# Adafruit_nRF52_Bluefruit_Feather.net
KiCad netlist of a schematic drawn in EAGLE
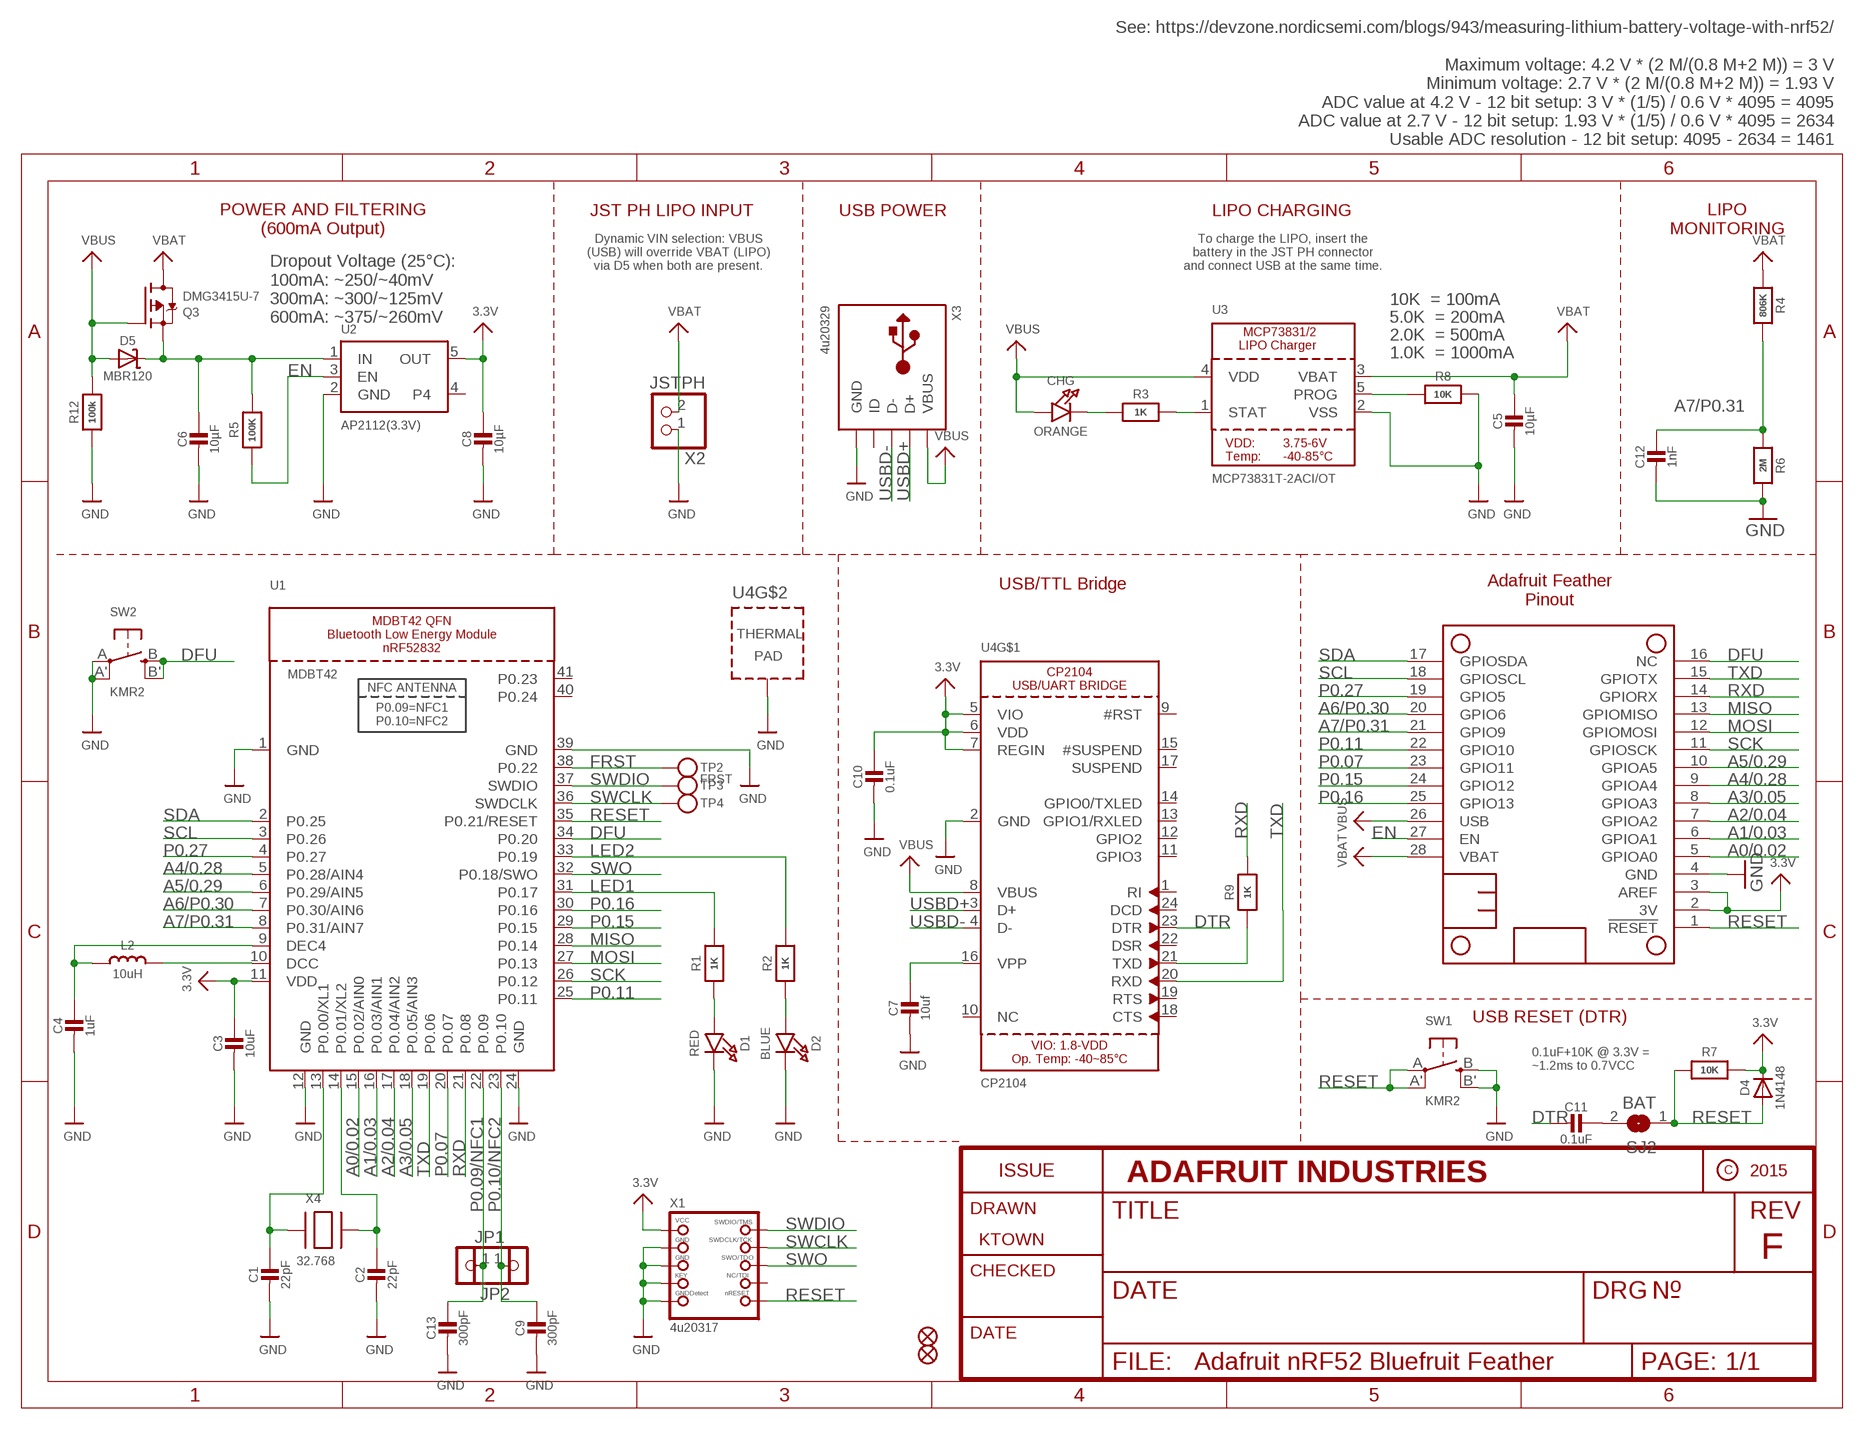
[diagram p0: schematic, sheet 1]

(export (version "E")
  (design (tool "Eeschema 10.0.6"))
  (components
    (comp (ref "C1")
      (value "22pF")
      (footprint "eagle-import:0603-NO")
      (libsource (lib "eagle-import") (part "CAP_CERAMIC0603_NO"))
    )
    (comp (ref "C2")
      (value "22pF")
      (footprint "eagle-import:0603-NO")
      (libsource (lib "eagle-import") (part "CAP_CERAMIC0603_NO"))
    )
    (comp (ref "C3")
      (value "10uF")
      (footprint "eagle-import:0805-NO")
      (libsource (lib "eagle-import") (part "CAP_CERAMIC0805-NOOUTLINE"))
    )
    (comp (ref "C4")
      (value "1uF")
      (footprint "eagle-import:0603-NO")
      (libsource (lib "eagle-import") (part "CAP_CERAMIC0603_NO"))
    )
    (comp (ref "C5")
      (value "10µF")
      (footprint "eagle-import:0805-NO")
      (libsource (lib "eagle-import") (part "CAP_CERAMIC0805-NOOUTLINE"))
    )
    (comp (ref "C6")
      (value "10µF")
      (footprint "eagle-import:0805-NO")
      (libsource (lib "eagle-import") (part "CAP_CERAMIC0805-NOOUTLINE"))
    )
    (comp (ref "C7")
      (value "10uf")
      (footprint "eagle-import:0805-NO")
      (libsource (lib "eagle-import") (part "CAP_CERAMIC0805-NOOUTLINE"))
    )
    (comp (ref "C8")
      (value "10µF")
      (footprint "eagle-import:0805-NO")
      (libsource (lib "eagle-import") (part "CAP_CERAMIC0805-NOOUTLINE"))
    )
    (comp (ref "C9")
      (value "300pF")
      (footprint "eagle-import:_0603MP")
      (libsource (lib "eagle-import") (part "CAP_CERAMIC_0603MP"))
    )
    (comp (ref "C10")
      (value "0.1uF")
      (footprint "eagle-import:0603-NO")
      (libsource (lib "eagle-import") (part "CAP_CERAMIC0603_NO"))
    )
    (comp (ref "C11")
      (value "0.1uF")
      (footprint "eagle-import:0603-NO")
      (libsource (lib "eagle-import") (part "CAP_CERAMIC0603_NO"))
    )
    (comp (ref "C12")
      (value "1nF")
      (footprint "eagle-import:0603-NO")
      (libsource (lib "eagle-import") (part "CAP_CERAMIC0603_NO"))
    )
    (comp (ref "C13")
      (value "300pF")
      (footprint "eagle-import:_0603MP")
      (libsource (lib "eagle-import") (part "CAP_CERAMIC_0603MP"))
    )
    (comp (ref "CHG")
      (value "ORANGE")
      (footprint "eagle-import:CHIPLED_0805_NOOUTLINE")
      (libsource (lib "eagle-import") (part "LED0805_NOOUTLINE"))
    )
    (comp (ref "D1")
      (value "RED")
      (footprint "eagle-import:CHIPLED_0805_NOOUTLINE")
      (libsource (lib "eagle-import") (part "LED0805_NOOUTLINE"))
    )
    (comp (ref "D2")
      (value "BLUE")
      (footprint "eagle-import:CHIPLED_0805_NOOUTLINE")
      (libsource (lib "eagle-import") (part "LED0805_NOOUTLINE"))
    )
    (comp (ref "D4")
      (value "1N4148")
      (footprint "eagle-import:SOD-323")
      (libsource (lib "eagle-import") (part "DIODESOD-323"))
    )
    (comp (ref "D5")
      (value "MBR120")
      (footprint "eagle-import:SOD-123")
      (libsource (lib "eagle-import") (part "DIODE-SCHOTTKYSOD-123"))
    )
    (comp (ref "FID1")
      (value "FIDUCIAL_1MM")
      (footprint "eagle-import:FIDUCIAL_1MM")
      (libsource (lib "eagle-import") (part "FIDUCIAL_1MM"))
    )
    (comp (ref "FID3")
      (value "FIDUCIAL_1MM")
      (footprint "eagle-import:FIDUCIAL_1MM")
      (libsource (lib "eagle-import") (part "FIDUCIAL_1MM"))
    )
    (comp (ref "JP1")
      (value "HEADER-1X12MM")
      (footprint "eagle-import:1X01_2MM")
      (libsource (lib "eagle-import") (part "HEADER-1X12MM"))
    )
    (comp (ref "JP2")
      (value "HEADER-1X12MM")
      (footprint "eagle-import:1X01_2MM")
      (libsource (lib "eagle-import") (part "HEADER-1X12MM"))
    )
    (comp (ref "L2")
      (value "10uH")
      (footprint "eagle-import:0805-NO")
      (libsource (lib "eagle-import") (part "INDUCTOR0805-NO"))
    )
    (comp (ref "MS1")
      (value "FEATHERWING_NODIM")
      (footprint "eagle-import:FEATHERWING_NODIM")
      (libsource (lib "eagle-import") (part "FEATHERWING_NODIM"))
    )
    (comp (ref "Q3")
      (value "DMG3415U-7")
      (footprint "eagle-import:SOT23-R")
      (libsource (lib "eagle-import") (part "MOSFET-P"))
    )
    (comp (ref "R1")
      (value "1K")
      (footprint "eagle-import:0603-NO")
      (libsource (lib "eagle-import") (part "RESISTOR_0603_NOOUT"))
    )
    (comp (ref "R2")
      (value "1K")
      (footprint "eagle-import:0603-NO")
      (libsource (lib "eagle-import") (part "RESISTOR_0603_NOOUT"))
    )
    (comp (ref "R3")
      (value "1K")
      (footprint "eagle-import:0603-NO")
      (libsource (lib "eagle-import") (part "RESISTOR_0603_NOOUT"))
    )
    (comp (ref "R4")
      (value "806K")
      (footprint "eagle-import:0603-NO")
      (libsource (lib "eagle-import") (part "RESISTOR_0603_NOOUT"))
    )
    (comp (ref "R5")
      (value "100K")
      (footprint "eagle-import:0603-NO")
      (libsource (lib "eagle-import") (part "RESISTOR_0603_NOOUT"))
    )
    (comp (ref "R6")
      (value "2M")
      (footprint "eagle-import:0603-NO")
      (libsource (lib "eagle-import") (part "RESISTOR_0603_NOOUT"))
    )
    (comp (ref "R7")
      (value "10K")
      (footprint "eagle-import:0603-NO")
      (libsource (lib "eagle-import") (part "RESISTOR_0603_NOOUT"))
    )
    (comp (ref "R8")
      (value "10K")
      (footprint "eagle-import:0603-NO")
      (libsource (lib "eagle-import") (part "RESISTOR_0603_NOOUT"))
    )
    (comp (ref "R9")
      (value "1K")
      (footprint "eagle-import:0603-NO")
      (libsource (lib "eagle-import") (part "RESISTOR_0603_NOOUT"))
    )
    (comp (ref "R12")
      (value "100k")
      (footprint "eagle-import:0603-NO")
      (libsource (lib "eagle-import") (part "RESISTOR_0603_NOOUT"))
    )
    (comp (ref "SJ2")
      (value "BAT")
      (footprint "eagle-import:SOLDERJUMPER_CLOSEDWIRE")
      (libsource (lib "eagle-import") (part "SOLDERJUMPERCLOSED"))
    )
    (comp (ref "SW1")
      (value "KMR2")
      (footprint "eagle-import:BTN_KMR2_4.6X2.8")
      (libsource (lib "eagle-import") (part "SWITCH_TACT_SMT4.6X2.8"))
    )
    (comp (ref "SW2")
      (value "KMR2")
      (footprint "eagle-import:BTN_KMR2_4.6X2.8")
      (libsource (lib "eagle-import") (part "SWITCH_TACT_SMT4.6X2.8"))
    )
    (comp (ref "TP2")
      (value "FRST")
      (footprint "eagle-import:PAD-1.5X2.0")
      (libsource (lib "eagle-import") (part "TESTPOINT1.5X2.0MM_NOCREAM"))
    )
    (comp (ref "TP3")
      (value "TESTPOINTROUND2MM")
      (footprint "eagle-import:TESTPOINT_ROUND_2MM")
      (libsource (lib "eagle-import") (part "TESTPOINTROUND2MM"))
    )
    (comp (ref "TP4")
      (value "TESTPOINTROUND2MM")
      (footprint "eagle-import:TESTPOINT_ROUND_2MM")
      (libsource (lib "eagle-import") (part "TESTPOINTROUND2MM"))
    )
    (comp (ref "U1")
      (value "MDBT42")
      (footprint "eagle-import:BLE_MODULE_RAYTAC_MDBT42")
      (libsource (lib "eagle-import") (part "NRF52832_MODULE_MDBT42"))
    )
    (comp (ref "U2")
      (value "AP2112(3.3V)")
      (footprint "eagle-import:SOT23-5")
      (libsource (lib "eagle-import") (part "VREG_SOT23-5"))
    )
    (comp (ref "U3")
      (value "MCP73831T-2ACI/OT")
      (footprint "eagle-import:SOT23-5")
      (libsource (lib "eagle-import") (part "MCP73831/2"))
    )
    (comp (ref "U4")
      (value "CP2104")
      (footprint "eagle-import:QFN24_4MM_SMSC")
      (libsource (lib "eagle-import") (part "CP2104"))
    )
    (comp (ref "X1")
      (value "4u20317")
      (footprint "eagle-import:2X05_1.27MM_BOX_POSTS")
      (libsource (lib "eagle-import") (part "JTAG-CORTEXBOXPOSTS"))
    )
    (comp (ref "X2")
      (value "JSTPH")
      (footprint "eagle-import:JSTPH2")
      (libsource (lib "eagle-import") (part "CON_JST_PH_2PIN"))
    )
    (comp (ref "X3")
      (value "4u20329")
      (footprint "eagle-import:4UCONN_20329_V2")
      (libsource (lib "eagle-import") (part "USB_MICRO_20329_V2"))
    )
    (comp (ref "X4")
      (value "32.768")
      (footprint "eagle-import:XTAL3215")
      (libsource (lib "eagle-import") (part "XTAL-3.2X1.5"))
    )
  )
  (nets
    (net (code "1") (name "/A0{slash}0.02") (class "Default")
      (node (ref "MS1") (pin "5") (pinfunction "GPIOA0_5") (pintype "bidirectional"))
      (node (ref "U1") (pin "15") (pinfunction "P0.02/AIN0_15") (pintype "bidirectional"))
    )
    (net (code "2") (name "/A1{slash}0.03") (class "Default")
      (node (ref "MS1") (pin "6") (pinfunction "GPIOA1_6") (pintype "bidirectional"))
      (node (ref "U1") (pin "16") (pinfunction "P0.03/AIN1_16") (pintype "bidirectional"))
    )
    (net (code "3") (name "/A2{slash}0.04") (class "Default")
      (node (ref "MS1") (pin "7") (pinfunction "GPIOA2_7") (pintype "bidirectional"))
      (node (ref "U1") (pin "17") (pinfunction "P0.04/AIN2_17") (pintype "bidirectional"))
    )
    (net (code "4") (name "/A3{slash}0.05") (class "Default")
      (node (ref "MS1") (pin "8") (pinfunction "GPIOA3_8") (pintype "bidirectional"))
      (node (ref "U1") (pin "18") (pinfunction "P0.05/AIN3_18") (pintype "bidirectional"))
    )
    (net (code "5") (name "/A4{slash}0.28") (class "Default")
      (node (ref "MS1") (pin "9") (pinfunction "GPIOA4_9") (pintype "bidirectional"))
      (node (ref "U1") (pin "5") (pinfunction "P0.28/AIN4_5") (pintype "bidirectional"))
    )
    (net (code "6") (name "/A5{slash}0.29") (class "Default")
      (node (ref "MS1") (pin "10") (pinfunction "GPIOA5_10") (pintype "bidirectional"))
      (node (ref "U1") (pin "6") (pinfunction "P0.29/AIN5_6") (pintype "bidirectional"))
    )
    (net (code "7") (name "/A6{slash}P0.30") (class "Default")
      (node (ref "MS1") (pin "20") (pinfunction "GPIO6_20") (pintype "bidirectional"))
      (node (ref "U1") (pin "7") (pinfunction "P0.30/AIN6_7") (pintype "bidirectional"))
    )
    (net (code "8") (name "/A7{slash}P0.31") (class "Default")
      (node (ref "C12") (pin "1") (pinfunction "1_1") (pintype "passive"))
      (node (ref "MS1") (pin "21") (pinfunction "GPIO9_21") (pintype "bidirectional"))
      (node (ref "R4") (pin "2") (pinfunction "2_2") (pintype "passive"))
      (node (ref "R6") (pin "1") (pinfunction "1_1") (pintype "passive"))
      (node (ref "U1") (pin "8") (pinfunction "P0.31/AIN7_8") (pintype "bidirectional"))
    )
    (net (code "9") (name "/DFU") (class "Default")
      (node (ref "MS1") (pin "16") (pinfunction "NC_16") (pintype "passive"))
      (node (ref "SW2") (pin "B") (pinfunction "S_B") (pintype "passive"))
      (node (ref "SW2") (pin "B'") (pinfunction "S1_B'") (pintype "passive"))
      (node (ref "U1") (pin "34") (pinfunction "P0.20_34") (pintype "bidirectional"))
    )
    (net (code "10") (name "/DTR") (class "Default")
      (node (ref "C11") (pin "2") (pinfunction "2_2") (pintype "passive"))
      (node (ref "U4") (pin "23") (pinfunction "DTR_23") (pintype "output"))
    )
    (net (code "11") (name "/EN") (class "Default")
      (node (ref "MS1") (pin "27") (pinfunction "EN_27") (pintype "passive"))
      (node (ref "R5") (pin "1") (pinfunction "1_1") (pintype "passive"))
      (node (ref "U2") (pin "3") (pinfunction "EN_3") (pintype "input"))
    )
    (net (code "12") (name "/FRST") (class "Default")
      (node (ref "TP2") (pin "P$1") (pinfunction "P$1_P$1") (pintype "bidirectional"))
      (node (ref "U1") (pin "38") (pinfunction "P0.22_38") (pintype "bidirectional"))
    )
    (net (code "13") (name "/LED1") (class "Default")
      (node (ref "R1") (pin "2") (pinfunction "2_2") (pintype "passive"))
      (node (ref "U1") (pin "31") (pinfunction "P0.17_31") (pintype "bidirectional"))
    )
    (net (code "14") (name "/LED2") (class "Default")
      (node (ref "R2") (pin "2") (pinfunction "2_2") (pintype "passive"))
      (node (ref "U1") (pin "33") (pinfunction "P0.19_33") (pintype "bidirectional"))
    )
    (net (code "15") (name "/MISO") (class "Default")
      (node (ref "MS1") (pin "13") (pinfunction "GPIOMISO_13") (pintype "bidirectional"))
      (node (ref "U1") (pin "28") (pinfunction "P0.14_28") (pintype "bidirectional"))
    )
    (net (code "16") (name "/MOSI") (class "Default")
      (node (ref "MS1") (pin "12") (pinfunction "GPIOMOSI_12") (pintype "bidirectional"))
      (node (ref "U1") (pin "27") (pinfunction "P0.13_27") (pintype "bidirectional"))
    )
    (net (code "17") (name "/P0.07") (class "Default")
      (node (ref "MS1") (pin "23") (pinfunction "GPIO11_23") (pintype "bidirectional"))
      (node (ref "U1") (pin "20") (pinfunction "P0.07_20") (pintype "bidirectional"))
    )
    (net (code "18") (name "/P0.09{slash}NFC1") (class "Default")
      (node (ref "C13") (pin "1") (pinfunction "1_1") (pintype "passive"))
      (node (ref "JP2") (pin "1") (pinfunction "1_1") (pintype "passive"))
      (node (ref "U1") (pin "22") (pinfunction "P0.09_22") (pintype "bidirectional"))
    )
    (net (code "19") (name "/P0.10{slash}NFC2") (class "Default")
      (node (ref "C9") (pin "1") (pinfunction "1_1") (pintype "passive"))
      (node (ref "JP1") (pin "1") (pinfunction "1_1") (pintype "passive"))
      (node (ref "U1") (pin "23") (pinfunction "P0.10_23") (pintype "bidirectional"))
    )
    (net (code "20") (name "/P0.11") (class "Default")
      (node (ref "MS1") (pin "22") (pinfunction "GPIO10_22") (pintype "bidirectional"))
      (node (ref "U1") (pin "25") (pinfunction "P0.11_25") (pintype "bidirectional"))
    )
    (net (code "21") (name "/P0.15") (class "Default")
      (node (ref "MS1") (pin "24") (pinfunction "GPIO12_24") (pintype "bidirectional"))
      (node (ref "U1") (pin "29") (pinfunction "P0.15_29") (pintype "bidirectional"))
    )
    (net (code "22") (name "/P0.16") (class "Default")
      (node (ref "MS1") (pin "25") (pinfunction "GPIO13_25") (pintype "bidirectional"))
      (node (ref "U1") (pin "30") (pinfunction "P0.16_30") (pintype "bidirectional"))
    )
    (net (code "23") (name "/P0.27") (class "Default")
      (node (ref "MS1") (pin "19") (pinfunction "GPIO5_19") (pintype "bidirectional"))
      (node (ref "U1") (pin "4") (pinfunction "P0.27_4") (pintype "bidirectional"))
    )
    (net (code "24") (name "/RESET") (class "Default")
      (node (ref "D4") (pin "A") (pinfunction "A_A") (pintype "passive"))
      (node (ref "MS1") (pin "1") (pinfunction "~{RESET}_1") (pintype "input"))
      (node (ref "R7") (pin "1") (pinfunction "1_1") (pintype "passive"))
      (node (ref "SJ2") (pin "1") (pinfunction "1_1") (pintype "passive"))
      (node (ref "SW1") (pin "A") (pinfunction "P_A") (pintype "passive"))
      (node (ref "SW1") (pin "A'") (pinfunction "P1_A'") (pintype "passive"))
      (node (ref "U1") (pin "35") (pinfunction "P0.21/RESET_35") (pintype "bidirectional"))
      (node (ref "X1") (pin "10") (pinfunction "NRESET_10") (pintype "bidirectional"))
    )
    (net (code "25") (name "/RXD") (class "Default")
      (node (ref "MS1") (pin "14") (pinfunction "GPIORX_14") (pintype "bidirectional"))
      (node (ref "R9") (pin "2") (pinfunction "2_2") (pintype "passive"))
      (node (ref "U1") (pin "21") (pinfunction "P0.08_21") (pintype "bidirectional"))
    )
    (net (code "26") (name "/SCK") (class "Default")
      (node (ref "MS1") (pin "11") (pinfunction "GPIOSCK_11") (pintype "bidirectional"))
      (node (ref "U1") (pin "26") (pinfunction "P0.12_26") (pintype "bidirectional"))
    )
    (net (code "27") (name "/SCL") (class "Default")
      (node (ref "MS1") (pin "18") (pinfunction "GPIOSCL_18") (pintype "bidirectional"))
      (node (ref "U1") (pin "3") (pinfunction "P0.26_3") (pintype "bidirectional"))
    )
    (net (code "28") (name "/SDA") (class "Default")
      (node (ref "MS1") (pin "17") (pinfunction "GPIOSDA_17") (pintype "bidirectional"))
      (node (ref "U1") (pin "2") (pinfunction "P0.25_2") (pintype "bidirectional"))
    )
    (net (code "29") (name "/SWCLK") (class "Default")
      (node (ref "TP4") (pin "P$1") (pinfunction "P$1_P$1") (pintype "bidirectional"))
      (node (ref "U1") (pin "36") (pinfunction "SWDCLK_36") (pintype "bidirectional"))
      (node (ref "X1") (pin "4") (pinfunction "SWDCLK_4") (pintype "bidirectional"))
    )
    (net (code "30") (name "/SWDIO") (class "Default")
      (node (ref "TP3") (pin "P$1") (pinfunction "P$1_P$1") (pintype "bidirectional"))
      (node (ref "U1") (pin "37") (pinfunction "SWDIO_37") (pintype "bidirectional"))
      (node (ref "X1") (pin "2") (pinfunction "SWDIO_2") (pintype "bidirectional"))
    )
    (net (code "31") (name "/SWO") (class "Default")
      (node (ref "U1") (pin "32") (pinfunction "P0.18/SWO_32") (pintype "bidirectional"))
      (node (ref "X1") (pin "6") (pinfunction "SWO_6") (pintype "bidirectional"))
    )
    (net (code "32") (name "/TXD") (class "Default")
      (node (ref "MS1") (pin "15") (pinfunction "GPIOTX_15") (pintype "bidirectional"))
      (node (ref "U1") (pin "19") (pinfunction "P0.06_19") (pintype "bidirectional"))
      (node (ref "U4") (pin "20") (pinfunction "RXD_20") (pintype "input"))
    )
    (net (code "33") (name "/USBD+") (class "Default")
      (node (ref "U4") (pin "3") (pinfunction "D+_3") (pintype "bidirectional"))
      (node (ref "X3") (pin "D+") (pinfunction "D+_D+") (pintype "bidirectional"))
    )
    (net (code "34") (name "/USBD-") (class "Default")
      (node (ref "U4") (pin "4") (pinfunction "D-_4") (pintype "bidirectional"))
      (node (ref "X3") (pin "D-") (pinfunction "D-_D-") (pintype "bidirectional"))
    )
    (net (code "35") (name "3.3V") (class "Default")
      (node (ref "C10") (pin "1") (pinfunction "1_1") (pintype "passive"))
      (node (ref "C3") (pin "1") (pinfunction "1_1") (pintype "passive"))
      (node (ref "C8") (pin "1") (pinfunction "1_1") (pintype "passive"))
      (node (ref "D4") (pin "C") (pinfunction "C_C") (pintype "passive"))
      (node (ref "MS1") (pin "2") (pinfunction "3V_2") (pintype "power_in"))
      (node (ref "MS1") (pin "3") (pinfunction "AREF_3") (pintype "passive"))
      (node (ref "R7") (pin "2") (pinfunction "2_2") (pintype "passive"))
      (node (ref "U1") (pin "11") (pinfunction "VDD_11") (pintype "bidirectional"))
      (node (ref "U2") (pin "5") (pinfunction "OUT_5") (pintype "power_in"))
      (node (ref "U4") (pin "5") (pinfunction "VIO_5") (pintype "power_in"))
      (node (ref "U4") (pin "6") (pinfunction "VDD_6") (pintype "power_in"))
      (node (ref "U4") (pin "7") (pinfunction "REGIN_7") (pintype "power_in"))
      (node (ref "X1") (pin "1") (pinfunction "VCC_1") (pintype "power_in"))
    )
    (net (code "36") (name "GND") (class "Default")
      (node (ref "C1") (pin "2") (pinfunction "2_2") (pintype "passive"))
      (node (ref "C10") (pin "2") (pinfunction "2_2") (pintype "passive"))
      (node (ref "C12") (pin "2") (pinfunction "2_2") (pintype "passive"))
      (node (ref "C13") (pin "2") (pinfunction "2_2") (pintype "passive"))
      (node (ref "C2") (pin "2") (pinfunction "2_2") (pintype "passive"))
      (node (ref "C3") (pin "2") (pinfunction "2_2") (pintype "passive"))
      (node (ref "C4") (pin "2") (pinfunction "2_2") (pintype "passive"))
      (node (ref "C5") (pin "2") (pinfunction "2_2") (pintype "passive"))
      (node (ref "C6") (pin "2") (pinfunction "2_2") (pintype "passive"))
      (node (ref "C7") (pin "2") (pinfunction "2_2") (pintype "passive"))
      (node (ref "C8") (pin "2") (pinfunction "2_2") (pintype "passive"))
      (node (ref "C9") (pin "2") (pinfunction "2_2") (pintype "passive"))
      (node (ref "D1") (pin "C") (pinfunction "C_C") (pintype "passive"))
      (node (ref "D2") (pin "C") (pinfunction "C_C") (pintype "passive"))
      (node (ref "MS1") (pin "4") (pinfunction "GND_4") (pintype "power_in"))
      (node (ref "R12") (pin "1") (pinfunction "1_1") (pintype "passive"))
      (node (ref "R6") (pin "2") (pinfunction "2_2") (pintype "passive"))
      (node (ref "R8") (pin "2") (pinfunction "2_2") (pintype "passive"))
      (node (ref "SW1") (pin "B") (pinfunction "S_B") (pintype "passive"))
      (node (ref "SW1") (pin "B'") (pinfunction "S1_B'") (pintype "passive"))
      (node (ref "SW2") (pin "A") (pinfunction "P_A") (pintype "passive"))
      (node (ref "SW2") (pin "A'") (pinfunction "P1_A'") (pintype "passive"))
      (node (ref "U1") (pin "1") (pinfunction "GND_1") (pintype "bidirectional"))
      (node (ref "U1") (pin "12") (pinfunction "GND_12") (pintype "bidirectional"))
      (node (ref "U1") (pin "24") (pinfunction "GND_24") (pintype "bidirectional"))
      (node (ref "U1") (pin "39") (pinfunction "GND_39") (pintype "bidirectional"))
      (node (ref "U2") (pin "2") (pinfunction "GND_2") (pintype "power_in"))
      (node (ref "U3") (pin "2") (pinfunction "VSS_2") (pintype "power_in"))
      (node (ref "U4") (pin "2") (pinfunction "GND_2") (pintype "power_in"))
      (node (ref "U4") (pin "THERM") (pinfunction "TP_THERM") (pintype "power_in"))
      (node (ref "X1") (pin "3") (pinfunction "GND_3") (pintype "power_in"))
      (node (ref "X1") (pin "5") (pinfunction "GND_5") (pintype "power_in"))
      (node (ref "X1") (pin "7") (pinfunction "KEY_7") (pintype "bidirectional"))
      (node (ref "X1") (pin "9") (pinfunction "GNDDETECT_9") (pintype "bidirectional"))
      (node (ref "X2") (pin "1") (pinfunction "1_1") (pintype "passive"))
      (node (ref "X3") (pin "BASE@1") (pinfunction "GND_BASE@1") (pintype "power_in"))
      (node (ref "X3") (pin "BASE@2") (pinfunction "GND_BASE@2") (pintype "power_in"))
      (node (ref "X3") (pin "GND") (pinfunction "GND_GND") (pintype "power_in"))
      (node (ref "X3") (pin "SPRT@1") (pinfunction "GND_SPRT@1") (pintype "power_in"))
      (node (ref "X3") (pin "SPRT@2") (pinfunction "GND_SPRT@2") (pintype "power_in"))
      (node (ref "X3") (pin "SPRT@3") (pinfunction "GND_SPRT@3") (pintype "power_in"))
      (node (ref "X3") (pin "SPRT@4") (pinfunction "GND_SPRT@4") (pintype "power_in"))
    )
    (net (code "37") (name "Net-(C11-Pad1)") (class "Default")
      (node (ref "C11") (pin "1") (pinfunction "1_1") (pintype "passive"))
      (node (ref "SJ2") (pin "2") (pinfunction "2_2") (pintype "passive"))
    )
    (net (code "38") (name "Net-(CHG-PadC)") (class "Default")
      (node (ref "CHG") (pin "C") (pinfunction "C_C") (pintype "passive"))
      (node (ref "R3") (pin "1") (pinfunction "1_1") (pintype "passive"))
    )
    (net (code "39") (name "Net-(D1-PadA)") (class "Default")
      (node (ref "D1") (pin "A") (pinfunction "A_A") (pintype "passive"))
      (node (ref "R1") (pin "1") (pinfunction "1_1") (pintype "passive"))
    )
    (net (code "40") (name "Net-(D2-PadA)") (class "Default")
      (node (ref "D2") (pin "A") (pinfunction "A_A") (pintype "passive"))
      (node (ref "R2") (pin "1") (pinfunction "1_1") (pintype "passive"))
    )
    (net (code "41") (name "Net-(Q3-S)") (class "Default")
      (node (ref "C6") (pin "1") (pinfunction "1_1") (pintype "passive"))
      (node (ref "D5") (pin "C") (pinfunction "C_C") (pintype "passive"))
      (node (ref "Q3") (pin "2") (pinfunction "S_2") (pintype "passive"))
      (node (ref "R5") (pin "2") (pinfunction "2_2") (pintype "passive"))
      (node (ref "U2") (pin "1") (pinfunction "IN_1") (pintype "power_in"))
    )
    (net (code "42") (name "Net-(U1-DCC)") (class "Default")
      (node (ref "L2") (pin "2") (pinfunction "2_2") (pintype "passive"))
      (node (ref "U1") (pin "10") (pinfunction "DCC_10") (pintype "bidirectional"))
    )
    (net (code "43") (name "Net-(U1-DEC4)") (class "Default")
      (node (ref "C4") (pin "1") (pinfunction "1_1") (pintype "passive"))
      (node (ref "L2") (pin "1") (pinfunction "1_1") (pintype "passive"))
      (node (ref "U1") (pin "9") (pinfunction "DEC4_9") (pintype "bidirectional"))
    )
    (net (code "44") (name "Net-(U1-P0.00{slash}XL1)") (class "Default")
      (node (ref "C1") (pin "1") (pinfunction "1_1") (pintype "passive"))
      (node (ref "U1") (pin "13") (pinfunction "P0.00/XL1_13") (pintype "bidirectional"))
      (node (ref "X4") (pin "P$1") (pinfunction "P$1_P$1") (pintype "bidirectional"))
    )
    (net (code "45") (name "Net-(U1-P0.01{slash}XL2)") (class "Default")
      (node (ref "C2") (pin "1") (pinfunction "1_1") (pintype "passive"))
      (node (ref "U1") (pin "14") (pinfunction "P0.01/XL2_14") (pintype "bidirectional"))
      (node (ref "X4") (pin "P$2") (pinfunction "P$2_P$2") (pintype "bidirectional"))
    )
    (net (code "46") (name "Net-(U3-PROG)") (class "Default")
      (node (ref "R8") (pin "1") (pinfunction "1_1") (pintype "passive"))
      (node (ref "U3") (pin "5") (pinfunction "PROG_5") (pintype "input"))
    )
    (net (code "47") (name "Net-(U3-STAT)") (class "Default")
      (node (ref "R3") (pin "2") (pinfunction "2_2") (pintype "passive"))
      (node (ref "U3") (pin "1") (pinfunction "STAT_1") (pintype "output"))
    )
    (net (code "48") (name "Net-(U4A-TXD)") (class "Default")
      (node (ref "R9") (pin "1") (pinfunction "1_1") (pintype "passive"))
      (node (ref "U4") (pin "21") (pinfunction "TXD_21") (pintype "output"))
    )
    (net (code "49") (name "Net-(U4A-VPP)") (class "Default")
      (node (ref "C7") (pin "1") (pinfunction "1_1") (pintype "passive"))
      (node (ref "U4") (pin "16") (pinfunction "VPP_16") (pintype "bidirectional"))
    )
    (net (code "50") (name "VBAT") (class "Default")
      (node (ref "C5") (pin "1") (pinfunction "1_1") (pintype "passive"))
      (node (ref "MS1") (pin "28") (pinfunction "VBAT_28") (pintype "power_in"))
      (node (ref "Q3") (pin "3") (pinfunction "D_3") (pintype "passive"))
      (node (ref "R4") (pin "1") (pinfunction "1_1") (pintype "passive"))
      (node (ref "U3") (pin "3") (pinfunction "VBAT_3") (pintype "power_in"))
      (node (ref "X2") (pin "2") (pinfunction "2_2") (pintype "passive"))
    )
    (net (code "51") (name "VBUS") (class "Default")
      (node (ref "CHG") (pin "A") (pinfunction "A_A") (pintype "passive"))
      (node (ref "D5") (pin "A") (pinfunction "A_A") (pintype "passive"))
      (node (ref "MS1") (pin "26") (pinfunction "USB_26") (pintype "power_in"))
      (node (ref "Q3") (pin "1") (pinfunction "G_1") (pintype "passive"))
      (node (ref "R12") (pin "2") (pinfunction "2_2") (pintype "passive"))
      (node (ref "U3") (pin "4") (pinfunction "VDD_4") (pintype "power_in"))
      (node (ref "U4") (pin "8") (pinfunction "VBUS_8") (pintype "power_in"))
      (node (ref "X3") (pin "VBUS") (pinfunction "VBUS_VBUS") (pintype "power_in"))
    )
    (net (code "52") (name "unconnected-(U1-P0.23-Pad41)") (class "Default")
      (node (ref "U1") (pin "41") (pinfunction "P0.23_41") (pintype "bidirectional"))
    )
    (net (code "53") (name "unconnected-(U1-P0.24-Pad40)") (class "Default")
      (node (ref "U1") (pin "40") (pinfunction "P0.24_40") (pintype "bidirectional"))
    )
    (net (code "54") (name "unconnected-(U2-P4-Pad4)") (class "Default")
      (node (ref "U2") (pin "4") (pinfunction "P4_4") (pintype "bidirectional"))
    )
    (net (code "55") (name "unconnected-(U4A-#RST-Pad9)") (class "Default")
      (node (ref "U4") (pin "9") (pinfunction "#RST_9") (pintype "bidirectional"))
    )
    (net (code "56") (name "unconnected-(U4A-#SUSPEND-Pad15)") (class "Default")
      (node (ref "U4") (pin "15") (pinfunction "#SUSPEND_15") (pintype "output"))
    )
    (net (code "57") (name "unconnected-(U4A-CTS-Pad18)") (class "Default")
      (node (ref "U4") (pin "18") (pinfunction "CTS_18") (pintype "input"))
    )
    (net (code "58") (name "unconnected-(U4A-DCD-Pad24)") (class "Default")
      (node (ref "U4") (pin "24") (pinfunction "DCD_24") (pintype "input"))
    )
    (net (code "59") (name "unconnected-(U4A-DSR-Pad22)") (class "Default")
      (node (ref "U4") (pin "22") (pinfunction "DSR_22") (pintype "input"))
    )
    (net (code "60") (name "unconnected-(U4A-GPIO0{slash}TXLED-Pad14)") (class "Default")
      (node (ref "U4") (pin "14") (pinfunction "GPIO0/TXLED_14") (pintype "bidirectional"))
    )
    (net (code "61") (name "unconnected-(U4A-GPIO1{slash}RXLED-Pad13)") (class "Default")
      (node (ref "U4") (pin "13") (pinfunction "GPIO1/RXLED_13") (pintype "bidirectional"))
    )
    (net (code "62") (name "unconnected-(U4A-GPIO2-Pad12)") (class "Default")
      (node (ref "U4") (pin "12") (pinfunction "GPIO2_12") (pintype "bidirectional"))
    )
    (net (code "63") (name "unconnected-(U4A-GPIO3-Pad11)") (class "Default")
      (node (ref "U4") (pin "11") (pinfunction "GPIO3_11") (pintype "bidirectional"))
    )
    (net (code "64") (name "unconnected-(U4A-NC-Pad10)") (class "Default")
      (node (ref "U4") (pin "10") (pinfunction "NC_10") (pintype "no_connect"))
    )
    (net (code "65") (name "unconnected-(U4A-RI-Pad1)") (class "Default")
      (node (ref "U4") (pin "1") (pinfunction "RI_1") (pintype "input"))
    )
    (net (code "66") (name "unconnected-(U4A-RTS-Pad19)") (class "Default")
      (node (ref "U4") (pin "19") (pinfunction "RTS_19") (pintype "output"))
    )
    (net (code "67") (name "unconnected-(U4A-SUSPEND-Pad17)") (class "Default")
      (node (ref "U4") (pin "17") (pinfunction "SUSPEND_17") (pintype "output"))
    )
    (net (code "68") (name "unconnected-(X1-TDI-Pad8)") (class "Default")
      (node (ref "X1") (pin "8") (pinfunction "TDI_8") (pintype "bidirectional"))
    )
    (net (code "69") (name "unconnected-(X3-PadID)") (class "Default")
      (node (ref "X3") (pin "ID") (pinfunction "ID_ID") (pintype "bidirectional"))
    )
  )
)
